# sb-sonata-fpganaalog.net
KiCad netlist of a schematic drawn in Altium Designer
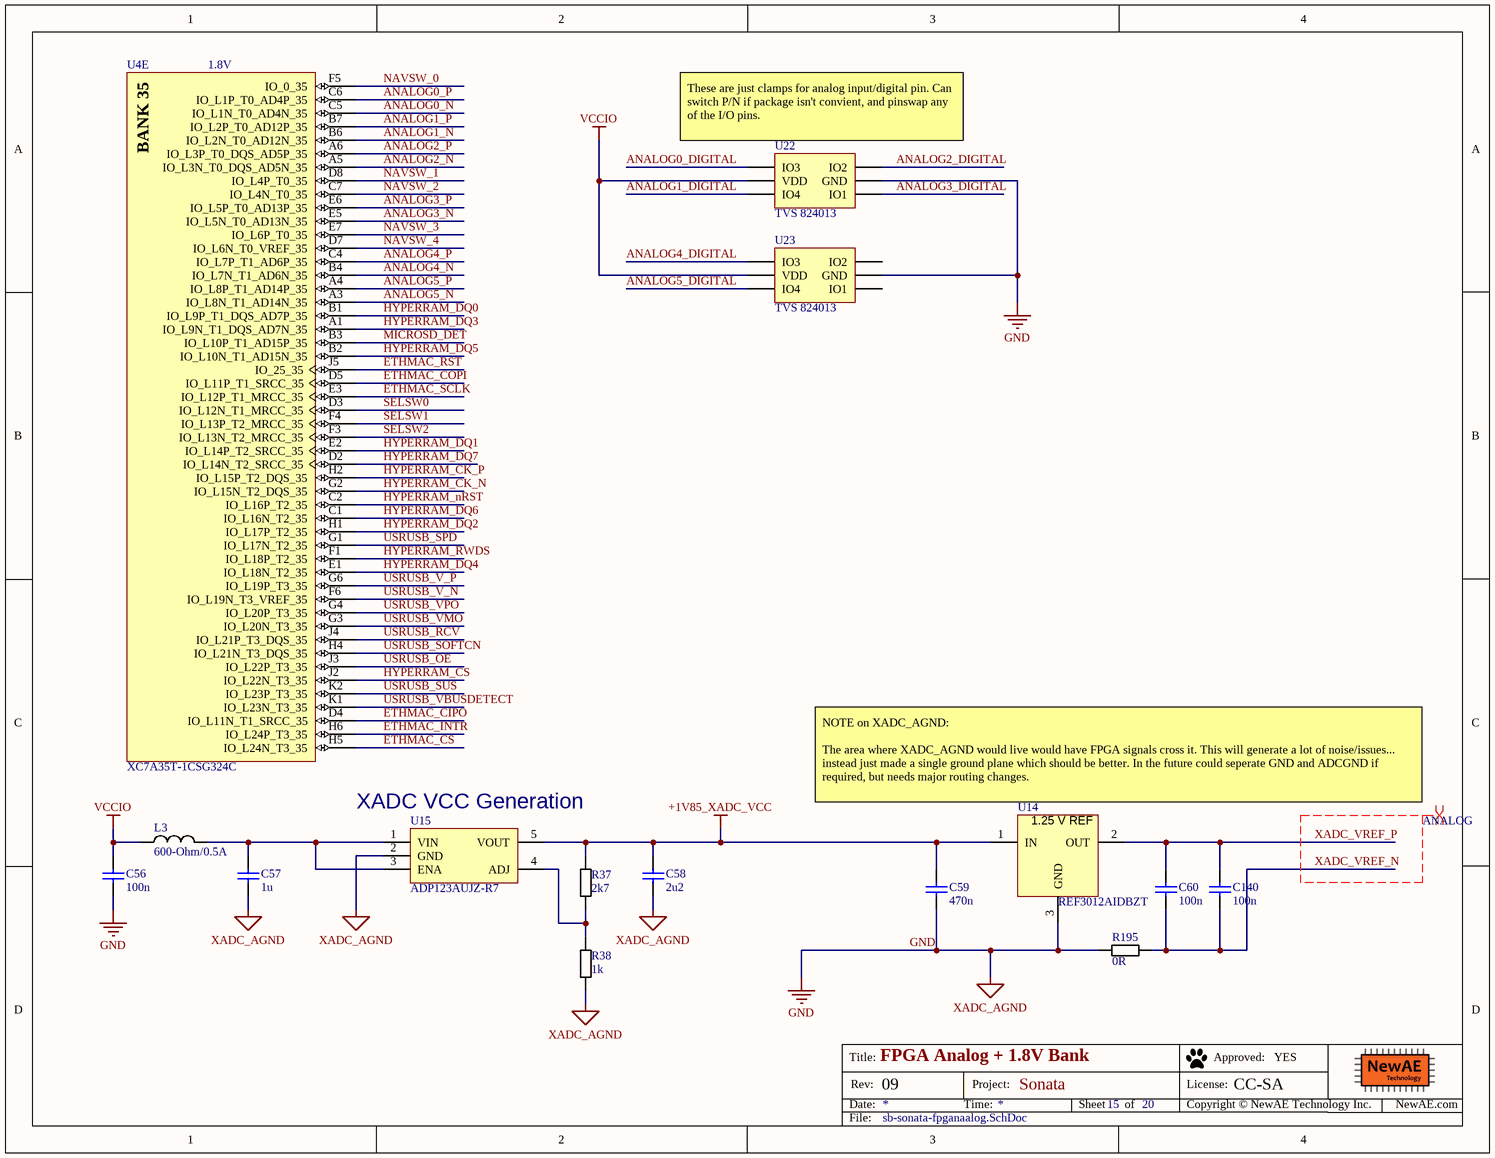
[diagram p0: sb-sonata-fpganaalog.SchDoc]

(export (version "E")
  (design (tool "Eeschema 10.0.6"))
  (components
    (comp (ref "C56")
      (value "100n")
      (footprint "CAPC0402_M")
      (description "100n, 0402")
      (fields (field (name "PART NUMBER") "CCHIP-100n-0402"))
      (libsource (lib "NewAE_AltiumLib") (part "CAP"))
    )
    (comp (ref "C57")
      (value "1u")
      (footprint "CAPC0603_M")
      (description "1u, 0603, 50V")
      (fields (field (name "PART NUMBER") "CCHIP-1u-0603"))
      (libsource (lib "NewAE_AltiumLib") (part "CAP"))
    )
    (comp (ref "C58")
      (value "2u2")
      (footprint "CAPC0603_M")
      (description "2u2, 0603")
      (fields (field (name "PART NUMBER") "CCHIP-2u2-0603-25V") (field (name "TOLERANCE") "±20%"))
      (libsource (lib "NewAE_AltiumLib") (part "CAP"))
    )
    (comp (ref "C59")
      (value "470n")
      (footprint "CAPC0603_M")
      (description "470n, 0603, 50V")
      (fields (field (name "PART NUMBER") "CCHIP-470n-0603-50V"))
      (libsource (lib "NewAE_AltiumLib") (part "CAP"))
    )
    (comp (ref "C60")
      (value "100n")
      (footprint "CAPC0402_M")
      (description "100n, 0402")
      (fields (field (name "PART NUMBER") "CCHIP-100n-0402"))
      (libsource (lib "NewAE_AltiumLib") (part "CAP"))
    )
    (comp (ref "C140")
      (value "100n")
      (footprint "CAPC0402_M")
      (description "100n, 0402")
      (fields (field (name "PART NUMBER") "CCHIP-100n-0402"))
      (libsource (lib "NewAE_AltiumLib") (part "CAP"))
    )
    (comp (ref "L3")
      (value "600-Ohm/0.5A")
      (footprint "IND_0603")
      (description "600 Ohm @ 100 MHz, 0.5A rated FB")
      (fields (field (name "PART NUMBER") "FBCHIP-600R-0603"))
      (libsource (lib "NewAE_AltiumLib") (part "IND"))
    )
    (comp (ref "R37")
      (value "2k7")
      (footprint "RESC1005X40N")
      (description "2k7 res, 0402, 1%, 1/16W")
      (fields (field (name "PART NUMBER") "RCHIP-2K7-0402") (field (name "TOLERANCE") "1%"))
      (libsource (lib "") (part "RES-EU_1"))
    )
    (comp (ref "R38")
      (value "1k")
      (footprint "RESC1005X40N")
      (description "1k res, 0402, 1%, 1/16W")
      (fields (field (name "PART NUMBER") "RCHIP-1K-0402") (field (name "TOLERANCE") "1%"))
      (libsource (lib "") (part "RES-EU_1"))
    )
    (comp (ref "R195")
      (value "0R")
      (footprint "RESC1005X40N")
      (description "2 ohm")
      (fields (field (name "PART NUMBER") "RCHIP-0R-0402"))
      (libsource (lib "NewAE_AltiumLib") (part "RES-EU"))
    )
    (comp (ref "U4")
      (value "XC7A35T-1CSG324C")
      (footprint "CSG324")
      (description "Artix-7 FPGA, 210 User I/Os, 0 GTP, 324-Ball BGA, Speed Grade 1, Commercial Grade, Pb-Free")
      (fields (field (name "MANUFACTURER") "Xilinx"))
      (libsource (lib "Altium Content Vault") (part "XLNX-XC7A35T-CSG324"))
    )
    (comp (ref "U14")
      (value "REF3012AIDBZT")
      (footprint "SOT95P237X112-3N")
      (description "IC VREF SERIES 0.2% SOT23-3")
      (fields (field (name "MANUFACTURER PART NUMBER") "REF3012AIDBZT"))
      (libsource (lib "NewAE_AltiumLib") (part "REF3012AIDBZT"))
    )
    (comp (ref "U15")
      (value "Linear Voltage Regulator IC  1 Output  300mA TSOT-5")
      (footprint "SOT23-5P95_285X145L45X40")
      (description "IC REG LIN POS ADJ 300MA TSOT5")
      (fields
        (field (name "MANUFACTURER PART NUMBER") "ADP123AUJZ-R7")
        (field (name "PART NUMBER") "ADP123AUJZ-R7")
      )
      (libsource (lib "NewAE_AltiumLib") (part "ADP123AUJZ-R7"))
    )
    (comp (ref "U22")
      (value "TVS 824013")
      (footprint "SOT95P280X145-6N")
      (description "TVS DIODE 3.3V 6V SOT23-6L")
      (fields (field (name "PART NUMBER") "TVS_4IO_3v3"))
      (libsource (lib "NewAE_AltiumLib") (part "IO_Clamp_x4_3v3_824013"))
    )
    (comp (ref "U23")
      (value "TVS 824013")
      (footprint "SOT95P280X145-6N")
      (description "TVS DIODE 3.3V 6V SOT23-6L")
      (fields (field (name "PART NUMBER") "TVS_4IO_3v3"))
      (libsource (lib "NewAE_AltiumLib") (part "IO_Clamp_x4_3v3_824013"))
    )
  )
  (nets
    (net (code "1") (name "+1V85_XADC_VCC") (class "Default")
      (node (ref "C58") (pin "1") (pinfunction "1_1") (pintype "passive"))
      (node (ref "C59") (pin "1") (pinfunction "1_1") (pintype "passive"))
      (node (ref "R37") (pin "1") (pinfunction "1_1") (pintype "passive"))
      (node (ref "U14") (pin "1") (pinfunction "IN_1") (pintype "passive"))
      (node (ref "U15") (pin "5") (pinfunction "VOUT_5") (pintype "passive"))
    )
    (net (code "2") (name "/ANALOG0_DIGITAL") (class "Default")
      (node (ref "U22") (pin "4") (pinfunction "IO3_4") (pintype "passive"))
    )
    (net (code "3") (name "/ANALOG0_N") (class "Default")
      (node (ref "U4") (pin "C5") (pinfunction "IO_L1N_T0_AD4N_35_C5") (pintype "bidirectional"))
    )
    (net (code "4") (name "/ANALOG0_P") (class "Default")
      (node (ref "U4") (pin "C6") (pinfunction "IO_L1P_T0_AD4P_35_C6") (pintype "bidirectional"))
    )
    (net (code "5") (name "/ANALOG1_DIGITAL") (class "Default")
      (node (ref "U22") (pin "6") (pinfunction "IO4_6") (pintype "passive"))
    )
    (net (code "6") (name "/ANALOG1_N") (class "Default")
      (node (ref "U4") (pin "B6") (pinfunction "IO_L2N_T0_AD12N_35_B6") (pintype "bidirectional"))
    )
    (net (code "7") (name "/ANALOG1_P") (class "Default")
      (node (ref "U4") (pin "B7") (pinfunction "IO_L2P_T0_AD12P_35_B7") (pintype "bidirectional"))
    )
    (net (code "8") (name "/ANALOG2_DIGITAL") (class "Default")
      (node (ref "U22") (pin "3") (pinfunction "IO2_3") (pintype "passive"))
    )
    (net (code "9") (name "/ANALOG2_N") (class "Default")
      (node (ref "U4") (pin "A5") (pinfunction "IO_L3N_T0_DQS_AD5N_35_A5") (pintype "bidirectional"))
    )
    (net (code "10") (name "/ANALOG2_P") (class "Default")
      (node (ref "U4") (pin "A6") (pinfunction "IO_L3P_T0_DQS_AD5P_35_A6") (pintype "bidirectional"))
    )
    (net (code "11") (name "/ANALOG3_DIGITAL") (class "Default")
      (node (ref "U22") (pin "1") (pinfunction "IO1_1") (pintype "passive"))
    )
    (net (code "12") (name "/ANALOG3_N") (class "Default")
      (node (ref "U4") (pin "E5") (pinfunction "IO_L5N_T0_AD13N_35_E5") (pintype "bidirectional"))
    )
    (net (code "13") (name "/ANALOG3_P") (class "Default")
      (node (ref "U4") (pin "E6") (pinfunction "IO_L5P_T0_AD13P_35_E6") (pintype "bidirectional"))
    )
    (net (code "14") (name "/ANALOG4_DIGITAL") (class "Default")
      (node (ref "U23") (pin "4") (pinfunction "IO3_4") (pintype "passive"))
    )
    (net (code "15") (name "/ANALOG4_N") (class "Default")
      (node (ref "U4") (pin "B4") (pinfunction "IO_L7N_T1_AD6N_35_B4") (pintype "bidirectional"))
    )
    (net (code "16") (name "/ANALOG4_P") (class "Default")
      (node (ref "U4") (pin "C4") (pinfunction "IO_L7P_T1_AD6P_35_C4") (pintype "bidirectional"))
    )
    (net (code "17") (name "/ANALOG5_DIGITAL") (class "Default")
      (node (ref "U23") (pin "6") (pinfunction "IO4_6") (pintype "passive"))
    )
    (net (code "18") (name "/ANALOG5_N") (class "Default")
      (node (ref "U4") (pin "A3") (pinfunction "IO_L8N_T1_AD14N_35_A3") (pintype "bidirectional"))
    )
    (net (code "19") (name "/ANALOG5_P") (class "Default")
      (node (ref "U4") (pin "A4") (pinfunction "IO_L8P_T1_AD14P_35_A4") (pintype "bidirectional"))
    )
    (net (code "20") (name "/ETHMAC_CIPO") (class "Default")
      (node (ref "U4") (pin "D4") (pinfunction "IO_L11N_T1_SRCC_35_D4") (pintype "bidirectional"))
    )
    (net (code "21") (name "/ETHMAC_COPI") (class "Default")
      (node (ref "U4") (pin "D5") (pinfunction "IO_L11P_T1_SRCC_35_D5") (pintype "bidirectional"))
    )
    (net (code "22") (name "/ETHMAC_CS") (class "Default")
      (node (ref "U4") (pin "H5") (pinfunction "IO_L24N_T3_35_H5") (pintype "bidirectional"))
    )
    (net (code "23") (name "/ETHMAC_INTR") (class "Default")
      (node (ref "U4") (pin "H6") (pinfunction "IO_L24P_T3_35_H6") (pintype "bidirectional"))
    )
    (net (code "24") (name "/ETHMAC_RST") (class "Default")
      (node (ref "U4") (pin "J5") (pinfunction "IO_25_35_J5") (pintype "bidirectional"))
    )
    (net (code "25") (name "/ETHMAC_SCLK") (class "Default")
      (node (ref "U4") (pin "E3") (pinfunction "IO_L12P_T1_MRCC_35_E3") (pintype "bidirectional"))
    )
    (net (code "26") (name "/HYPERRAM_CK_N") (class "Default")
      (node (ref "U4") (pin "G2") (pinfunction "IO_L15N_T2_DQS_35_G2") (pintype "bidirectional"))
    )
    (net (code "27") (name "/HYPERRAM_CK_P") (class "Default")
      (node (ref "U4") (pin "H2") (pinfunction "IO_L15P_T2_DQS_35_H2") (pintype "bidirectional"))
    )
    (net (code "28") (name "/HYPERRAM_CS") (class "Default")
      (node (ref "U4") (pin "J2") (pinfunction "IO_L22N_T3_35_J2") (pintype "bidirectional"))
    )
    (net (code "29") (name "/HYPERRAM_DQ0") (class "Default")
      (node (ref "U4") (pin "B1") (pinfunction "IO_L9P_T1_DQS_AD7P_35_B1") (pintype "bidirectional"))
    )
    (net (code "30") (name "/HYPERRAM_DQ1") (class "Default")
      (node (ref "U4") (pin "E2") (pinfunction "IO_L14P_T2_SRCC_35_E2") (pintype "bidirectional"))
    )
    (net (code "31") (name "/HYPERRAM_DQ2") (class "Default")
      (node (ref "U4") (pin "H1") (pinfunction "IO_L17P_T2_35_H1") (pintype "bidirectional"))
    )
    (net (code "32") (name "/HYPERRAM_DQ3") (class "Default")
      (node (ref "U4") (pin "A1") (pinfunction "IO_L9N_T1_DQS_AD7N_35_A1") (pintype "bidirectional"))
    )
    (net (code "33") (name "/HYPERRAM_DQ4") (class "Default")
      (node (ref "U4") (pin "E1") (pinfunction "IO_L18N_T2_35_E1") (pintype "bidirectional"))
    )
    (net (code "34") (name "/HYPERRAM_DQ5") (class "Default")
      (node (ref "U4") (pin "B2") (pinfunction "IO_L10N_T1_AD15N_35_B2") (pintype "bidirectional"))
    )
    (net (code "35") (name "/HYPERRAM_DQ6") (class "Default")
      (node (ref "U4") (pin "C1") (pinfunction "IO_L16N_T2_35_C1") (pintype "bidirectional"))
    )
    (net (code "36") (name "/HYPERRAM_DQ7") (class "Default")
      (node (ref "U4") (pin "D2") (pinfunction "IO_L14N_T2_SRCC_35_D2") (pintype "bidirectional"))
    )
    (net (code "37") (name "/HYPERRAM_RWDS") (class "Default")
      (node (ref "U4") (pin "F1") (pinfunction "IO_L18P_T2_35_F1") (pintype "bidirectional"))
    )
    (net (code "38") (name "/HYPERRAM_nRST") (class "Default")
      (node (ref "U4") (pin "C2") (pinfunction "IO_L16P_T2_35_C2") (pintype "bidirectional"))
    )
    (net (code "39") (name "/MICROSD_DET") (class "Default")
      (node (ref "U4") (pin "B3") (pinfunction "IO_L10P_T1_AD15P_35_B3") (pintype "bidirectional"))
    )
    (net (code "40") (name "/NAVSW_0") (class "Default")
      (node (ref "U4") (pin "F5") (pinfunction "IO_0_35_F5") (pintype "bidirectional"))
    )
    (net (code "41") (name "/NAVSW_1") (class "Default")
      (node (ref "U4") (pin "D8") (pinfunction "IO_L4P_T0_35_D8") (pintype "bidirectional"))
    )
    (net (code "42") (name "/NAVSW_2") (class "Default")
      (node (ref "U4") (pin "C7") (pinfunction "IO_L4N_T0_35_C7") (pintype "bidirectional"))
    )
    (net (code "43") (name "/NAVSW_3") (class "Default")
      (node (ref "U4") (pin "E7") (pinfunction "IO_L6P_T0_35_E7") (pintype "bidirectional"))
    )
    (net (code "44") (name "/NAVSW_4") (class "Default")
      (node (ref "U4") (pin "D7") (pinfunction "IO_L6N_T0_VREF_35_D7") (pintype "bidirectional"))
    )
    (net (code "45") (name "/SELSW0") (class "Default")
      (node (ref "U4") (pin "D3") (pinfunction "IO_L12N_T1_MRCC_35_D3") (pintype "bidirectional"))
    )
    (net (code "46") (name "/SELSW1") (class "Default")
      (node (ref "U4") (pin "F4") (pinfunction "IO_L13P_T2_MRCC_35_F4") (pintype "bidirectional"))
    )
    (net (code "47") (name "/SELSW2") (class "Default")
      (node (ref "U4") (pin "F3") (pinfunction "IO_L13N_T2_MRCC_35_F3") (pintype "bidirectional"))
    )
    (net (code "48") (name "/USRUSB_OE") (class "Default")
      (node (ref "U4") (pin "J3") (pinfunction "IO_L22P_T3_35_J3") (pintype "bidirectional"))
    )
    (net (code "49") (name "/USRUSB_RCV") (class "Default")
      (node (ref "U4") (pin "J4") (pinfunction "IO_L21P_T3_DQS_35_J4") (pintype "bidirectional"))
    )
    (net (code "50") (name "/USRUSB_SOFTCN") (class "Default")
      (node (ref "U4") (pin "H4") (pinfunction "IO_L21N_T3_DQS_35_H4") (pintype "bidirectional"))
    )
    (net (code "51") (name "/USRUSB_SPD") (class "Default")
      (node (ref "U4") (pin "G1") (pinfunction "IO_L17N_T2_35_G1") (pintype "bidirectional"))
    )
    (net (code "52") (name "/USRUSB_SUS") (class "Default")
      (node (ref "U4") (pin "K2") (pinfunction "IO_L23P_T3_35_K2") (pintype "bidirectional"))
    )
    (net (code "53") (name "/USRUSB_VBUSDETECT") (class "Default")
      (node (ref "U4") (pin "K1") (pinfunction "IO_L23N_T3_35_K1") (pintype "bidirectional"))
    )
    (net (code "54") (name "/USRUSB_VMO") (class "Default")
      (node (ref "U4") (pin "G3") (pinfunction "IO_L20N_T3_35_G3") (pintype "bidirectional"))
    )
    (net (code "55") (name "/USRUSB_VPO") (class "Default")
      (node (ref "U4") (pin "G4") (pinfunction "IO_L20P_T3_35_G4") (pintype "bidirectional"))
    )
    (net (code "56") (name "/USRUSB_V_N") (class "Default")
      (node (ref "U4") (pin "F6") (pinfunction "IO_L19N_T3_VREF_35_F6") (pintype "bidirectional"))
    )
    (net (code "57") (name "/USRUSB_V_P") (class "Default")
      (node (ref "U4") (pin "G6") (pinfunction "IO_L19P_T3_35_G6") (pintype "bidirectional"))
    )
    (net (code "58") (name "/XADC_VREF_N") (class "Default")
      (node (ref "C140") (pin "2") (pinfunction "2_2") (pintype "passive"))
      (node (ref "C60") (pin "2") (pinfunction "2_2") (pintype "passive"))
      (node (ref "R195") (pin "2") (pinfunction "2_2") (pintype "passive"))
    )
    (net (code "59") (name "/XADC_VREF_P") (class "Default")
      (node (ref "C140") (pin "1") (pinfunction "1_1") (pintype "passive"))
      (node (ref "C60") (pin "1") (pinfunction "1_1") (pintype "passive"))
      (node (ref "U14") (pin "2") (pinfunction "OUT_2") (pintype "passive"))
    )
    (net (code "60") (name "GND") (class "Default")
      (node (ref "C56") (pin "2") (pinfunction "2_2") (pintype "passive"))
      (node (ref "C57") (pin "2") (pinfunction "2_2") (pintype "passive"))
      (node (ref "C58") (pin "2") (pinfunction "2_2") (pintype "passive"))
      (node (ref "C59") (pin "2") (pinfunction "2_2") (pintype "passive"))
      (node (ref "R195") (pin "1") (pinfunction "1_1") (pintype "passive"))
      (node (ref "R38") (pin "2") (pinfunction "2_2") (pintype "passive"))
      (node (ref "U14") (pin "3") (pinfunction "GND_3") (pintype "passive"))
      (node (ref "U15") (pin "2") (pinfunction "GND_2") (pintype "passive"))
      (node (ref "U22") (pin "2") (pinfunction "GND_2") (pintype "passive"))
      (node (ref "U23") (pin "2") (pinfunction "GND_2") (pintype "passive"))
    )
    (net (code "61") (name "Net-(U15-ADJ)") (class "Default")
      (node (ref "R37") (pin "2") (pinfunction "2_2") (pintype "passive"))
      (node (ref "R38") (pin "1") (pinfunction "1_1") (pintype "passive"))
      (node (ref "U15") (pin "4") (pinfunction "ADJ_4") (pintype "passive"))
    )
    (net (code "62") (name "Net-(U15-ENA)") (class "Default")
      (node (ref "C57") (pin "1") (pinfunction "1_1") (pintype "passive"))
      (node (ref "L3") (pin "2") (pinfunction "2_2") (pintype "passive"))
      (node (ref "U15") (pin "1") (pinfunction "VIN_1") (pintype "passive"))
      (node (ref "U15") (pin "3") (pinfunction "ENA_3") (pintype "passive"))
    )
    (net (code "63") (name "VCCIO") (class "Default")
      (node (ref "C56") (pin "1") (pinfunction "1_1") (pintype "passive"))
      (node (ref "L3") (pin "1") (pinfunction "1_1") (pintype "passive"))
      (node (ref "U22") (pin "5") (pinfunction "VDD_5") (pintype "passive"))
      (node (ref "U23") (pin "5") (pinfunction "VDD_5") (pintype "passive"))
    )
    (net (code "64") (name "unconnected-(U23-IO1-Pad1)") (class "Default")
      (node (ref "U23") (pin "1") (pinfunction "IO1_1") (pintype "passive"))
    )
    (net (code "65") (name "unconnected-(U23-IO2-Pad3)") (class "Default")
      (node (ref "U23") (pin "3") (pinfunction "IO2_3") (pintype "passive"))
    )
  )
)
